# Main.net
KiCad netlist of a schematic drawn in EAGLE
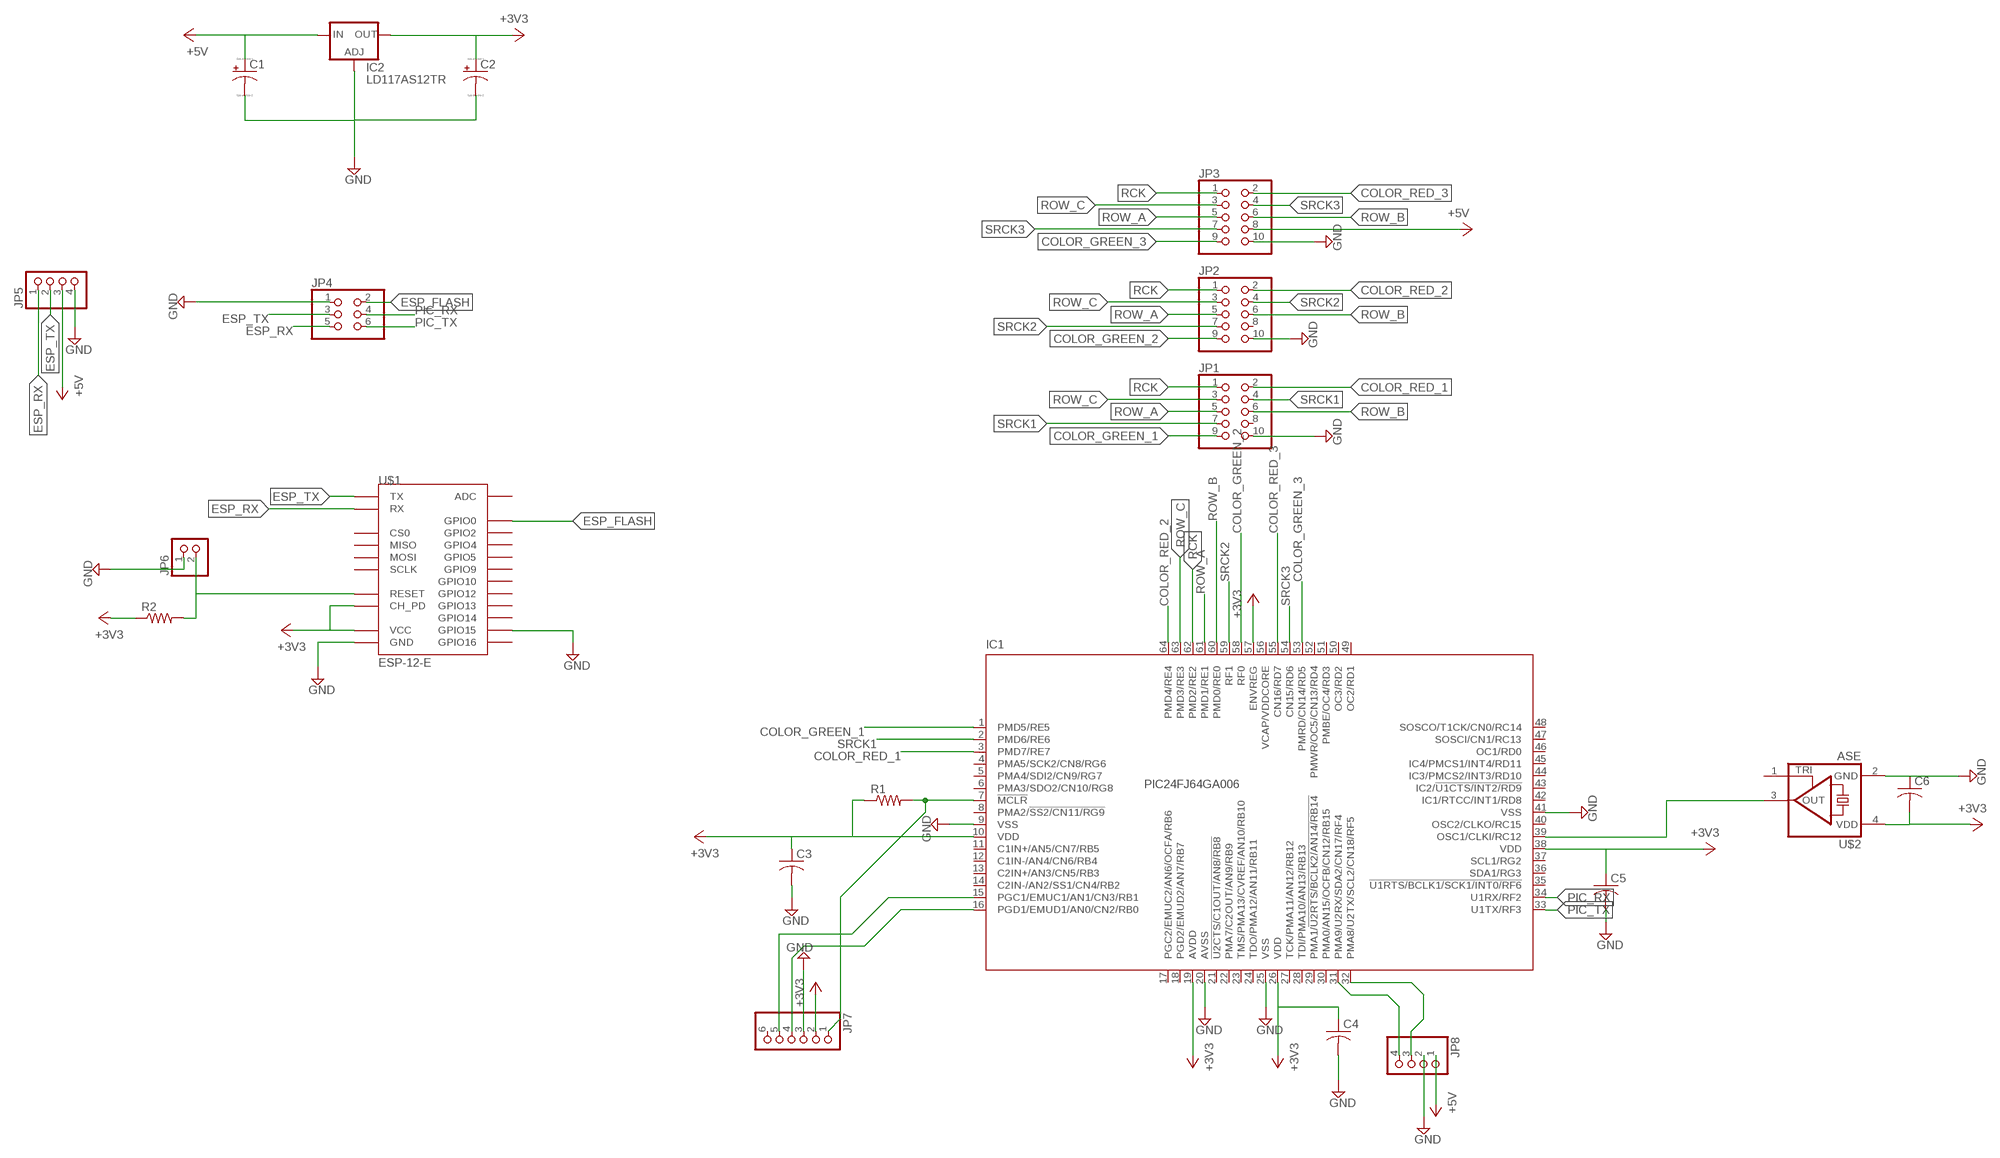
[diagram p0: schematic, sheet 1]

(export (version "E")
  (design (tool "Eeschema 10.0.6"))
  (components
    (comp (ref "C1")
      (value "CPOL-USB/3528-21W")
      (footprint "eagle-import:B_3528-21W")
      (libsource (lib "eagle-import") (part "CPOL-USB/3528-21W"))
    )
    (comp (ref "C2")
      (value "CPOL-USB/3528-21W")
      (footprint "eagle-import:B_3528-21W")
      (libsource (lib "eagle-import") (part "CPOL-USB/3528-21W"))
    )
    (comp (ref "C3")
      (value "C-USC0603K")
      (footprint "eagle-import:C0603K")
      (libsource (lib "eagle-import") (part "C-USC0603K"))
    )
    (comp (ref "C4")
      (value "C-USC0603K")
      (footprint "eagle-import:C0603K")
      (libsource (lib "eagle-import") (part "C-USC0603K"))
    )
    (comp (ref "C5")
      (value "C-USC0603K")
      (footprint "eagle-import:C0603K")
      (libsource (lib "eagle-import") (part "C-USC0603K"))
    )
    (comp (ref "C6")
      (value "C-USC0603K")
      (footprint "eagle-import:C0603K")
      (libsource (lib "eagle-import") (part "C-USC0603K"))
    )
    (comp (ref "IC1")
      (value "PIC24FJ64GA006")
      (footprint "eagle-import:TQFP64-10X10")
      (fields (field (name "MPN") "PIC24FJ64GA006-I/PT"))
      (libsource (lib "eagle-import") (part "PIC24FJGA00664"))
    )
    (comp (ref "IC2")
      (value "LD117AS12TR")
      (footprint "eagle-import:SOT223")
      (libsource (lib "eagle-import") (part "LD117A?S12TR"))
    )
    (comp (ref "JP1")
      (value "PINHD-2X5")
      (footprint "eagle-import:2X05")
      (libsource (lib "eagle-import") (part "PINHD-2X5"))
    )
    (comp (ref "JP2")
      (value "PINHD-2X5")
      (footprint "eagle-import:2X05")
      (libsource (lib "eagle-import") (part "PINHD-2X5"))
    )
    (comp (ref "JP3")
      (value "PINHD-2X5")
      (footprint "eagle-import:2X05")
      (libsource (lib "eagle-import") (part "PINHD-2X5"))
    )
    (comp (ref "JP4")
      (value "PINHD-2X3")
      (footprint "eagle-import:2X03")
      (libsource (lib "eagle-import") (part "PINHD-2X3"))
    )
    (comp (ref "JP5")
      (value "PINHD-1X4")
      (footprint "eagle-import:1X04")
      (libsource (lib "eagle-import") (part "PINHD-1X4"))
    )
    (comp (ref "JP6")
      (value "PINHD-1X2")
      (footprint "eagle-import:1X02")
      (libsource (lib "eagle-import") (part "PINHD-1X2"))
    )
    (comp (ref "JP7")
      (value "PINHD-1X6")
      (footprint "eagle-import:1X06")
      (libsource (lib "eagle-import") (part "PINHD-1X6"))
    )
    (comp (ref "JP8")
      (value "PINHD-1X4")
      (footprint "eagle-import:1X04")
      (libsource (lib "eagle-import") (part "PINHD-1X4"))
    )
    (comp (ref "R1")
      (value "R-US_MELF0102W")
      (footprint "eagle-import:MINI_MELF-0102W")
      (libsource (lib "eagle-import") (part "R-US_MELF0102W"))
    )
    (comp (ref "R2")
      (value "R-US_MELF0102W")
      (footprint "eagle-import:MINI_MELF-0102W")
      (libsource (lib "eagle-import") (part "R-US_MELF0102W"))
    )
    (comp (ref "U$1")
      (value "ESP-12-E")
      (footprint "eagle-import:ESP-12-E")
      (libsource (lib "eagle-import") (part "ESP-12-E"))
    )
    (comp (ref "U$2")
      (value "ASE")
      (footprint "eagle-import:ASE")
      (libsource (lib "eagle-import") (part "ASE"))
    )
  )
  (nets
    (net (code "1") (name "+3V3") (class "Default")
      (node (ref "C2") (pin "+") (pinfunction "+_+") (pintype "passive"))
      (node (ref "C3") (pin "1") (pinfunction "1_1") (pintype "passive"))
      (node (ref "C4") (pin "1") (pinfunction "1_1") (pintype "passive"))
      (node (ref "C5") (pin "1") (pinfunction "1_1") (pintype "passive"))
      (node (ref "C6") (pin "2") (pinfunction "2_2") (pintype "passive"))
      (node (ref "IC1") (pin "10") (pinfunction "VDD_10") (pintype "power_in"))
      (node (ref "IC1") (pin "19") (pinfunction "AVDD_19") (pintype "power_in"))
      (node (ref "IC1") (pin "26") (pinfunction "VDD_26") (pintype "power_in"))
      (node (ref "IC1") (pin "38") (pinfunction "VDD_38") (pintype "power_in"))
      (node (ref "IC1") (pin "57") (pinfunction "ENVREG_57") (pintype "bidirectional"))
      (node (ref "IC2") (pin "4") (pinfunction "OUT_4") (pintype "passive"))
      (node (ref "JP7") (pin "2") (pinfunction "2_2") (pintype "passive"))
      (node (ref "R1") (pin "1") (pinfunction "1_1") (pintype "passive"))
      (node (ref "R2") (pin "1") (pinfunction "1_1") (pintype "passive"))
      (node (ref "U$1") (pin "CH_PD") (pinfunction "CH_PD_CH_PD") (pintype "bidirectional"))
      (node (ref "U$1") (pin "VCC") (pinfunction "VCC_VCC") (pintype "bidirectional"))
      (node (ref "U$2") (pin "4") (pinfunction "VDD_4") (pintype "power_in"))
    )
    (net (code "2") (name "+5V") (class "Default")
      (node (ref "C1") (pin "+") (pinfunction "+_+") (pintype "passive"))
      (node (ref "IC2") (pin "3") (pinfunction "IN_3") (pintype "input"))
      (node (ref "JP3") (pin "8") (pinfunction "8_8") (pintype "passive"))
      (node (ref "JP5") (pin "3") (pinfunction "3_3") (pintype "passive"))
      (node (ref "JP8") (pin "1") (pinfunction "1_1") (pintype "passive"))
    )
    (net (code "3") (name "COLOR_GREEN_1") (class "Default")
      (node (ref "IC1") (pin "1") (pinfunction "PMD5/RE5_1") (pintype "bidirectional"))
      (node (ref "JP1") (pin "9") (pinfunction "9_9") (pintype "passive"))
    )
    (net (code "4") (name "COLOR_GREEN_2") (class "Default")
      (node (ref "IC1") (pin "58") (pinfunction "RF0_58") (pintype "bidirectional"))
      (node (ref "JP2") (pin "9") (pinfunction "9_9") (pintype "passive"))
    )
    (net (code "5") (name "COLOR_GREEN_3") (class "Default")
      (node (ref "IC1") (pin "53") (pinfunction "PMRD/CN14/RD5_53") (pintype "bidirectional"))
      (node (ref "JP3") (pin "9") (pinfunction "9_9") (pintype "passive"))
    )
    (net (code "6") (name "COLOR_RED_1") (class "Default")
      (node (ref "IC1") (pin "3") (pinfunction "PMD7/RE7_3") (pintype "bidirectional"))
      (node (ref "JP1") (pin "2") (pinfunction "2_2") (pintype "passive"))
    )
    (net (code "7") (name "COLOR_RED_2") (class "Default")
      (node (ref "IC1") (pin "64") (pinfunction "PMD4/RE4_64") (pintype "bidirectional"))
      (node (ref "JP2") (pin "2") (pinfunction "2_2") (pintype "passive"))
    )
    (net (code "8") (name "COLOR_RED_3") (class "Default")
      (node (ref "IC1") (pin "55") (pinfunction "CN16/RD7_55") (pintype "bidirectional"))
      (node (ref "JP3") (pin "2") (pinfunction "2_2") (pintype "passive"))
    )
    (net (code "9") (name "ESP_FLASH") (class "Default")
      (node (ref "JP4") (pin "2") (pinfunction "2_2") (pintype "passive"))
      (node (ref "U$1") (pin "GPIO0") (pinfunction "GPIO0_GPIO0") (pintype "bidirectional"))
    )
    (net (code "10") (name "ESP_RX") (class "Default")
      (node (ref "JP4") (pin "5") (pinfunction "5_5") (pintype "passive"))
      (node (ref "JP5") (pin "1") (pinfunction "1_1") (pintype "passive"))
      (node (ref "U$1") (pin "RX") (pinfunction "RX_RX") (pintype "bidirectional"))
    )
    (net (code "11") (name "ESP_TX") (class "Default")
      (node (ref "JP4") (pin "3") (pinfunction "3_3") (pintype "passive"))
      (node (ref "JP5") (pin "2") (pinfunction "2_2") (pintype "passive"))
      (node (ref "U$1") (pin "TX") (pinfunction "TX_TX") (pintype "bidirectional"))
    )
    (net (code "12") (name "GND") (class "Default")
      (node (ref "C1") (pin "-") (pinfunction "-_-") (pintype "passive"))
      (node (ref "C2") (pin "-") (pinfunction "-_-") (pintype "passive"))
      (node (ref "C3") (pin "2") (pinfunction "2_2") (pintype "passive"))
      (node (ref "C4") (pin "2") (pinfunction "2_2") (pintype "passive"))
      (node (ref "C5") (pin "2") (pinfunction "2_2") (pintype "passive"))
      (node (ref "C6") (pin "1") (pinfunction "1_1") (pintype "passive"))
      (node (ref "IC1") (pin "20") (pinfunction "AVSS_20") (pintype "power_in"))
      (node (ref "IC1") (pin "25") (pinfunction "VSS_25") (pintype "power_in"))
      (node (ref "IC1") (pin "41") (pinfunction "VSS_41") (pintype "power_in"))
      (node (ref "IC1") (pin "9") (pinfunction "VSS_9") (pintype "power_in"))
      (node (ref "IC2") (pin "1") (pinfunction "ADJ_1") (pintype "input"))
      (node (ref "JP1") (pin "10") (pinfunction "10_10") (pintype "passive"))
      (node (ref "JP2") (pin "10") (pinfunction "10_10") (pintype "passive"))
      (node (ref "JP3") (pin "10") (pinfunction "10_10") (pintype "passive"))
      (node (ref "JP4") (pin "1") (pinfunction "1_1") (pintype "passive"))
      (node (ref "JP5") (pin "4") (pinfunction "4_4") (pintype "passive"))
      (node (ref "JP6") (pin "1") (pinfunction "1_1") (pintype "passive"))
      (node (ref "JP7") (pin "3") (pinfunction "3_3") (pintype "passive"))
      (node (ref "JP8") (pin "2") (pinfunction "2_2") (pintype "passive"))
      (node (ref "U$1") (pin "GND") (pinfunction "GND_GND") (pintype "bidirectional"))
      (node (ref "U$1") (pin "GPIO15") (pinfunction "GPIO15_GPIO15") (pintype "bidirectional"))
      (node (ref "U$2") (pin "2") (pinfunction "GND_2") (pintype "power_in"))
    )
    (net (code "13") (name "Net-(IC1-OSC1{slash}CLKI{slash}RC12)") (class "Default")
      (node (ref "IC1") (pin "39") (pinfunction "OSC1/CLKI/RC12_39") (pintype "bidirectional"))
      (node (ref "U$2") (pin "3") (pinfunction "OUT_3") (pintype "output"))
    )
    (net (code "14") (name "Net-(IC1-PGC1{slash}EMUC1{slash}AN1{slash}CN3{slash}RB1)") (class "Default")
      (node (ref "IC1") (pin "15") (pinfunction "PGC1/EMUC1/AN1/CN3/RB1_15") (pintype "bidirectional"))
      (node (ref "JP7") (pin "5") (pinfunction "5_5") (pintype "passive"))
    )
    (net (code "15") (name "Net-(IC1-PGD1{slash}EMUD1{slash}AN0{slash}CN2{slash}RB0)") (class "Default")
      (node (ref "IC1") (pin "16") (pinfunction "PGD1/EMUD1/AN0/CN2/RB0_16") (pintype "bidirectional"))
      (node (ref "JP7") (pin "4") (pinfunction "4_4") (pintype "passive"))
    )
    (net (code "16") (name "Net-(IC1-PMA8{slash}U2TX{slash}SCL2{slash}CN18{slash}RF5)") (class "Default")
      (node (ref "IC1") (pin "32") (pinfunction "PMA8/U2TX/SCL2/CN18/RF5_32") (pintype "bidirectional"))
      (node (ref "JP8") (pin "3") (pinfunction "3_3") (pintype "passive"))
    )
    (net (code "17") (name "Net-(IC1-PMA9{slash}U2RX{slash}SDA2{slash}CN17{slash}RF4)") (class "Default")
      (node (ref "IC1") (pin "31") (pinfunction "PMA9/U2RX/SDA2/CN17/RF4_31") (pintype "bidirectional"))
      (node (ref "JP8") (pin "4") (pinfunction "4_4") (pintype "passive"))
    )
    (net (code "18") (name "Net-(IC1-~{MCLR})") (class "Default")
      (node (ref "IC1") (pin "7") (pinfunction "~{MCLR}_7") (pintype "bidirectional"))
      (node (ref "JP7") (pin "1") (pinfunction "1_1") (pintype "passive"))
      (node (ref "R1") (pin "2") (pinfunction "2_2") (pintype "passive"))
    )
    (net (code "19") (name "Net-(JP6-Pad2)") (class "Default")
      (node (ref "JP6") (pin "2") (pinfunction "2_2") (pintype "passive"))
      (node (ref "R2") (pin "2") (pinfunction "2_2") (pintype "passive"))
      (node (ref "U$1") (pin "RESET") (pinfunction "RESET_RESET") (pintype "bidirectional"))
    )
    (net (code "20") (name "PIC_RX") (class "Default")
      (node (ref "IC1") (pin "34") (pinfunction "U1RX/RF2_34") (pintype "bidirectional"))
      (node (ref "JP4") (pin "4") (pinfunction "4_4") (pintype "passive"))
    )
    (net (code "21") (name "PIC_TX") (class "Default")
      (node (ref "IC1") (pin "33") (pinfunction "U1TX/RF3_33") (pintype "bidirectional"))
      (node (ref "JP4") (pin "6") (pinfunction "6_6") (pintype "passive"))
    )
    (net (code "22") (name "RCK") (class "Default")
      (node (ref "IC1") (pin "62") (pinfunction "PMD2/RE2_62") (pintype "bidirectional"))
      (node (ref "JP1") (pin "1") (pinfunction "1_1") (pintype "passive"))
      (node (ref "JP2") (pin "1") (pinfunction "1_1") (pintype "passive"))
      (node (ref "JP3") (pin "1") (pinfunction "1_1") (pintype "passive"))
    )
    (net (code "23") (name "ROW_A") (class "Default")
      (node (ref "IC1") (pin "61") (pinfunction "PMD1/RE1_61") (pintype "bidirectional"))
      (node (ref "JP1") (pin "5") (pinfunction "5_5") (pintype "passive"))
      (node (ref "JP2") (pin "5") (pinfunction "5_5") (pintype "passive"))
      (node (ref "JP3") (pin "5") (pinfunction "5_5") (pintype "passive"))
    )
    (net (code "24") (name "ROW_B") (class "Default")
      (node (ref "IC1") (pin "60") (pinfunction "PMD0/RE0_60") (pintype "bidirectional"))
      (node (ref "JP1") (pin "6") (pinfunction "6_6") (pintype "passive"))
      (node (ref "JP2") (pin "6") (pinfunction "6_6") (pintype "passive"))
      (node (ref "JP3") (pin "6") (pinfunction "6_6") (pintype "passive"))
    )
    (net (code "25") (name "ROW_C") (class "Default")
      (node (ref "IC1") (pin "63") (pinfunction "PMD3/RE3_63") (pintype "bidirectional"))
      (node (ref "JP1") (pin "3") (pinfunction "3_3") (pintype "passive"))
      (node (ref "JP2") (pin "3") (pinfunction "3_3") (pintype "passive"))
      (node (ref "JP3") (pin "3") (pinfunction "3_3") (pintype "passive"))
    )
    (net (code "26") (name "SRCK1") (class "Default")
      (node (ref "IC1") (pin "2") (pinfunction "PMD6/RE6_2") (pintype "bidirectional"))
      (node (ref "JP1") (pin "4") (pinfunction "4_4") (pintype "passive"))
      (node (ref "JP1") (pin "7") (pinfunction "7_7") (pintype "passive"))
    )
    (net (code "27") (name "SRCK2") (class "Default")
      (node (ref "IC1") (pin "59") (pinfunction "RF1_59") (pintype "bidirectional"))
      (node (ref "JP2") (pin "4") (pinfunction "4_4") (pintype "passive"))
      (node (ref "JP2") (pin "7") (pinfunction "7_7") (pintype "passive"))
    )
    (net (code "28") (name "SRCK3") (class "Default")
      (node (ref "IC1") (pin "54") (pinfunction "CN15/RD6_54") (pintype "bidirectional"))
      (node (ref "JP3") (pin "4") (pinfunction "4_4") (pintype "passive"))
      (node (ref "JP3") (pin "7") (pinfunction "7_7") (pintype "passive"))
    )
    (net (code "29") (name "unconnected-(IC1-C1IN+{slash}AN5{slash}CN7{slash}RB5-Pad11)") (class "Default")
      (node (ref "IC1") (pin "11") (pinfunction "C1IN+/AN5/CN7/RB5_11") (pintype "bidirectional"))
    )
    (net (code "30") (name "unconnected-(IC1-C1IN-{slash}AN4{slash}CN6{slash}RB4-Pad12)") (class "Default")
      (node (ref "IC1") (pin "12") (pinfunction "C1IN-/AN4/CN6/RB4_12") (pintype "bidirectional"))
    )
    (net (code "31") (name "unconnected-(IC1-C2IN+{slash}AN3{slash}CN5{slash}RB3-Pad13)") (class "Default")
      (node (ref "IC1") (pin "13") (pinfunction "C2IN+/AN3/CN5/RB3_13") (pintype "bidirectional"))
    )
    (net (code "32") (name "unconnected-(IC1-C2IN-{slash}AN2{slash}SS1{slash}CN4{slash}RB2-Pad14)") (class "Default")
      (node (ref "IC1") (pin "14") (pinfunction "C2IN-/AN2/SS1/CN4/RB2_14") (pintype "bidirectional"))
    )
    (net (code "33") (name "unconnected-(IC1-IC1{slash}RTCC{slash}INT1{slash}RD8-Pad42)") (class "Default")
      (node (ref "IC1") (pin "42") (pinfunction "IC1/RTCC/INT1/RD8_42") (pintype "bidirectional"))
    )
    (net (code "34") (name "unconnected-(IC1-IC2{slash}~{U1CTS{slash}INT2{slash}RD9}-Pad43)") (class "Default")
      (node (ref "IC1") (pin "43") (pinfunction "IC2/~{U1CTS/INT2/RD9}_43") (pintype "bidirectional"))
    )
    (net (code "35") (name "unconnected-(IC1-IC3{slash}PMCS2{slash}INT3{slash}RD10-Pad44)") (class "Default")
      (node (ref "IC1") (pin "44") (pinfunction "IC3/PMCS2/INT3/RD10_44") (pintype "bidirectional"))
    )
    (net (code "36") (name "unconnected-(IC1-IC4{slash}PMCS1{slash}INT4{slash}RD11-Pad45)") (class "Default")
      (node (ref "IC1") (pin "45") (pinfunction "IC4/PMCS1/INT4/RD11_45") (pintype "bidirectional"))
    )
    (net (code "37") (name "unconnected-(IC1-OC1{slash}RD0-Pad46)") (class "Default")
      (node (ref "IC1") (pin "46") (pinfunction "OC1/RD0_46") (pintype "bidirectional"))
    )
    (net (code "38") (name "unconnected-(IC1-OC2{slash}RD1-Pad49)") (class "Default")
      (node (ref "IC1") (pin "49") (pinfunction "OC2/RD1_49") (pintype "bidirectional"))
    )
    (net (code "39") (name "unconnected-(IC1-OC3{slash}RD2-Pad50)") (class "Default")
      (node (ref "IC1") (pin "50") (pinfunction "OC3/RD2_50") (pintype "bidirectional"))
    )
    (net (code "40") (name "unconnected-(IC1-OSC2{slash}CLKO{slash}RC15-Pad40)") (class "Default")
      (node (ref "IC1") (pin "40") (pinfunction "OSC2/CLKO/RC15_40") (pintype "bidirectional"))
    )
    (net (code "41") (name "unconnected-(IC1-PGC2{slash}EMUC2{slash}AN6{slash}OCFA{slash}RB6-Pad17)") (class "Default")
      (node (ref "IC1") (pin "17") (pinfunction "PGC2/EMUC2/AN6/OCFA/RB6_17") (pintype "bidirectional"))
    )
    (net (code "42") (name "unconnected-(IC1-PGD2{slash}EMUD2{slash}AN7{slash}RB7-Pad18)") (class "Default")
      (node (ref "IC1") (pin "18") (pinfunction "PGD2/EMUD2/AN7/RB7_18") (pintype "bidirectional"))
    )
    (net (code "43") (name "unconnected-(IC1-PMA0{slash}AN15{slash}OCFB{slash}CN12{slash}RB15-Pad30)") (class "Default")
      (node (ref "IC1") (pin "30") (pinfunction "PMA0/AN15/OCFB/CN12/RB15_30") (pintype "bidirectional"))
    )
    (net (code "44") (name "unconnected-(IC1-PMA1{slash}~{U2RTS{slash}BCLK2{slash}AN14{slash}RB14}-Pad29)") (class "Default")
      (node (ref "IC1") (pin "29") (pinfunction "PMA1/~{U2RTS/BCLK2/AN14/RB14}_29") (pintype "bidirectional"))
    )
    (net (code "45") (name "unconnected-(IC1-PMA2{slash}~{SS2{slash}CN11{slash}RG9}-Pad8)") (class "Default")
      (node (ref "IC1") (pin "8") (pinfunction "PMA2/~{SS2/CN11/RG9}_8") (pintype "bidirectional"))
    )
    (net (code "46") (name "unconnected-(IC1-PMA3{slash}SDO2{slash}CN10{slash}RG8-Pad6)") (class "Default")
      (node (ref "IC1") (pin "6") (pinfunction "PMA3/SDO2/CN10/RG8_6") (pintype "bidirectional"))
    )
    (net (code "47") (name "unconnected-(IC1-PMA4{slash}SDI2{slash}CN9{slash}RG7-Pad5)") (class "Default")
      (node (ref "IC1") (pin "5") (pinfunction "PMA4/SDI2/CN9/RG7_5") (pintype "bidirectional"))
    )
    (net (code "48") (name "unconnected-(IC1-PMA5{slash}SCK2{slash}CN8{slash}RG6-Pad4)") (class "Default")
      (node (ref "IC1") (pin "4") (pinfunction "PMA5/SCK2/CN8/RG6_4") (pintype "bidirectional"))
    )
    (net (code "49") (name "unconnected-(IC1-PMA7{slash}C2OUT{slash}AN9{slash}RB9-Pad22)") (class "Default")
      (node (ref "IC1") (pin "22") (pinfunction "PMA7/C2OUT/AN9/RB9_22") (pintype "bidirectional"))
    )
    (net (code "50") (name "unconnected-(IC1-PMBE{slash}OC4{slash}RD3-Pad51)") (class "Default")
      (node (ref "IC1") (pin "51") (pinfunction "PMBE/OC4/RD3_51") (pintype "bidirectional"))
    )
    (net (code "51") (name "unconnected-(IC1-PMWR{slash}OC5{slash}CN13{slash}RD4-Pad52)") (class "Default")
      (node (ref "IC1") (pin "52") (pinfunction "PMWR/OC5/CN13/RD4_52") (pintype "bidirectional"))
    )
    (net (code "52") (name "unconnected-(IC1-SCL1{slash}RG2-Pad37)") (class "Default")
      (node (ref "IC1") (pin "37") (pinfunction "SCL1/RG2_37") (pintype "bidirectional"))
    )
    (net (code "53") (name "unconnected-(IC1-SDA1{slash}RG3-Pad36)") (class "Default")
      (node (ref "IC1") (pin "36") (pinfunction "SDA1/RG3_36") (pintype "bidirectional"))
    )
    (net (code "54") (name "unconnected-(IC1-SOSCI{slash}CN1{slash}RC13-Pad47)") (class "Default")
      (node (ref "IC1") (pin "47") (pinfunction "SOSCI/CN1/RC13_47") (pintype "bidirectional"))
    )
    (net (code "55") (name "unconnected-(IC1-SOSCO{slash}T1CK{slash}CN0{slash}RC14-Pad48)") (class "Default")
      (node (ref "IC1") (pin "48") (pinfunction "SOSCO/T1CK/CN0/RC14_48") (pintype "bidirectional"))
    )
    (net (code "56") (name "unconnected-(IC1-TCK{slash}PMA11{slash}AN12{slash}RB12-Pad27)") (class "Default")
      (node (ref "IC1") (pin "27") (pinfunction "TCK/PMA11/AN12/RB12_27") (pintype "bidirectional"))
    )
    (net (code "57") (name "unconnected-(IC1-TDI{slash}PMA10{slash}AN13{slash}RB13-Pad28)") (class "Default")
      (node (ref "IC1") (pin "28") (pinfunction "TDI/PMA10/AN13/RB13_28") (pintype "bidirectional"))
    )
    (net (code "58") (name "unconnected-(IC1-TDO{slash}PMA12{slash}AN11{slash}RB11-Pad24)") (class "Default")
      (node (ref "IC1") (pin "24") (pinfunction "TDO/PMA12/AN11/RB11_24") (pintype "bidirectional"))
    )
    (net (code "59") (name "unconnected-(IC1-TMS{slash}PMA13{slash}CVREF{slash}AN10{slash}RB10-Pad23)") (class "Default")
      (node (ref "IC1") (pin "23") (pinfunction "TMS/PMA13/CVREF/AN10/RB10_23") (pintype "bidirectional"))
    )
    (net (code "60") (name "unconnected-(IC1-VCAP{slash}VDDCORE-Pad56)") (class "Default")
      (node (ref "IC1") (pin "56") (pinfunction "VCAP/VDDCORE_56") (pintype "bidirectional"))
    )
    (net (code "61") (name "unconnected-(IC1-~{U1RTS{slash}BCLK1{slash}SCK1{slash}INT0{slash}RF6}-Pad35)") (class "Default")
      (node (ref "IC1") (pin "35") (pinfunction "~{U1RTS/BCLK1/SCK1/INT0/RF6}_35") (pintype "bidirectional"))
    )
    (net (code "62") (name "unconnected-(IC1-~{U2CTS{slash}C1OUT{slash}AN8{slash}RB8}-Pad21)") (class "Default")
      (node (ref "IC1") (pin "21") (pinfunction "~{U2CTS/C1OUT/AN8/RB8}_21") (pintype "bidirectional"))
    )
    (net (code "63") (name "unconnected-(JP1-Pad8)") (class "Default")
      (node (ref "JP1") (pin "8") (pinfunction "8_8") (pintype "passive"))
    )
    (net (code "64") (name "unconnected-(JP2-Pad8)") (class "Default")
      (node (ref "JP2") (pin "8") (pinfunction "8_8") (pintype "passive"))
    )
    (net (code "65") (name "unconnected-(JP7-Pad6)") (class "Default")
      (node (ref "JP7") (pin "6") (pinfunction "6_6") (pintype "passive"))
    )
    (net (code "66") (name "unconnected-(U$1-PadADC)") (class "Default")
      (node (ref "U$1") (pin "ADC") (pinfunction "ADC_ADC") (pintype "bidirectional"))
    )
    (net (code "67") (name "unconnected-(U$1-PadCS0)") (class "Default")
      (node (ref "U$1") (pin "CS0") (pinfunction "CS0_CS0") (pintype "bidirectional"))
    )
    (net (code "68") (name "unconnected-(U$1-PadGPIO2)") (class "Default")
      (node (ref "U$1") (pin "GPIO2") (pinfunction "GPIO2_GPIO2") (pintype "bidirectional"))
    )
    (net (code "69") (name "unconnected-(U$1-PadGPIO4)") (class "Default")
      (node (ref "U$1") (pin "GPIO4") (pinfunction "GPIO4_GPIO4") (pintype "bidirectional"))
    )
    (net (code "70") (name "unconnected-(U$1-PadGPIO5)") (class "Default")
      (node (ref "U$1") (pin "GPIO5") (pinfunction "GPIO5_GPIO5") (pintype "bidirectional"))
    )
    (net (code "71") (name "unconnected-(U$1-PadGPIO9)") (class "Default")
      (node (ref "U$1") (pin "GPIO9") (pinfunction "GPIO9_GPIO9") (pintype "bidirectional"))
    )
    (net (code "72") (name "unconnected-(U$1-PadGPIO10)") (class "Default")
      (node (ref "U$1") (pin "GPIO10") (pinfunction "GPIO10_GPIO10") (pintype "bidirectional"))
    )
    (net (code "73") (name "unconnected-(U$1-PadGPIO12)") (class "Default")
      (node (ref "U$1") (pin "GPIO12") (pinfunction "GPIO12_GPIO12") (pintype "bidirectional"))
    )
    (net (code "74") (name "unconnected-(U$1-PadGPIO13)") (class "Default")
      (node (ref "U$1") (pin "GPIO13") (pinfunction "GPIO13_GPIO13") (pintype "bidirectional"))
    )
    (net (code "75") (name "unconnected-(U$1-PadGPIO14)") (class "Default")
      (node (ref "U$1") (pin "GPIO14") (pinfunction "GPIO14_GPIO14") (pintype "bidirectional"))
    )
    (net (code "76") (name "unconnected-(U$1-PadGPIO16)") (class "Default")
      (node (ref "U$1") (pin "GPIO16") (pinfunction "GPIO16_GPIO16") (pintype "bidirectional"))
    )
    (net (code "77") (name "unconnected-(U$1-PadMISO)") (class "Default")
      (node (ref "U$1") (pin "MISO") (pinfunction "MISO_MISO") (pintype "bidirectional"))
    )
    (net (code "78") (name "unconnected-(U$1-PadMOSI)") (class "Default")
      (node (ref "U$1") (pin "MOSI") (pinfunction "MOSI_MOSI") (pintype "bidirectional"))
    )
    (net (code "79") (name "unconnected-(U$1-PadSCLK)") (class "Default")
      (node (ref "U$1") (pin "SCLK") (pinfunction "SCLK_SCLK") (pintype "bidirectional"))
    )
    (net (code "80") (name "unconnected-(U$2-TRI-Pad1)") (class "Default")
      (node (ref "U$2") (pin "1") (pinfunction "TRI_1") (pintype "input"))
    )
  )
)
